# battery_box2.net
KiCad netlist of a schematic drawn in EAGLE
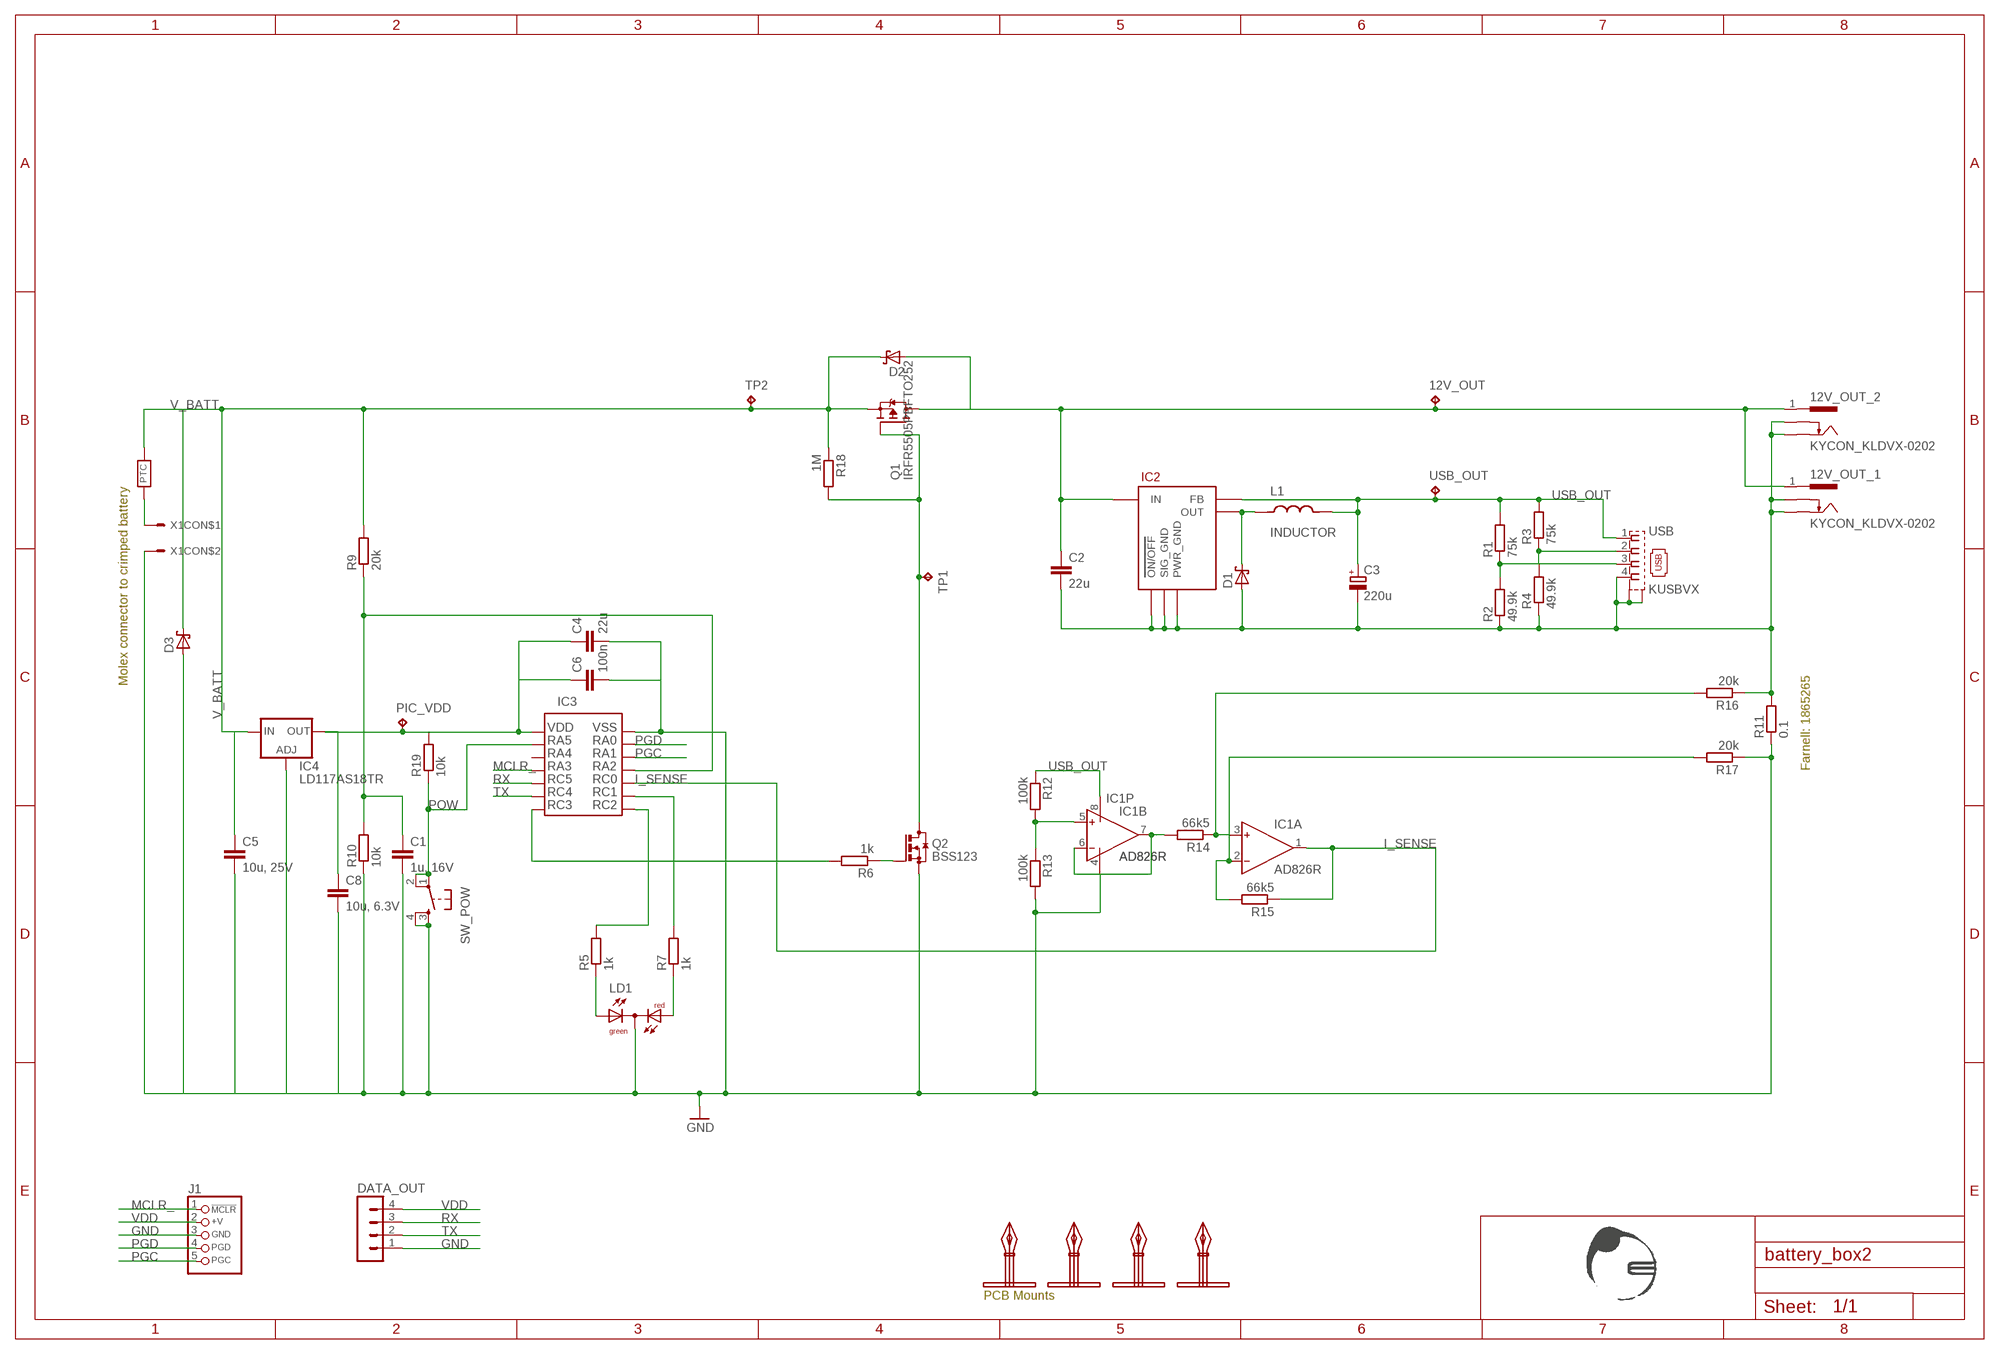
[diagram p0: schematic, sheet 1]

(export (version "E")
  (design (tool "Eeschema 10.0.6"))
  (components
    (comp (ref "12V_OUT")
      (value "TPTP20R")
      (footprint "eagle-import:TP20R")
      (libsource (lib "eagle-import") (part "TPTP20R"))
    )
    (comp (ref "12V_OUT_1")
      (value "KYCON_KLDVX-0202")
      (footprint "eagle-import:KYCON_KLVDX_2020_B")
      (libsource (lib "eagle-import") (part "KYCON_KLDVX-0202"))
    )
    (comp (ref "12V_OUT_2")
      (value "KYCON_KLDVX-0202")
      (footprint "eagle-import:KYCON_KLVDX_2020_B")
      (libsource (lib "eagle-import") (part "KYCON_KLDVX-0202"))
    )
    (comp (ref "C1")
      (value "1u, 16V")
      (footprint "eagle-import:C0805")
      (libsource (lib "eagle-import") (part "C-EUC0805"))
    )
    (comp (ref "C2")
      (value "22u")
      (footprint "eagle-import:C1210")
      (libsource (lib "eagle-import") (part "C-EUC1210"))
    )
    (comp (ref "C3")
      (value "220u")
      (footprint "eagle-import:PANASONIC_E")
      (libsource (lib "eagle-import") (part "CPOL-EUE"))
    )
    (comp (ref "C4")
      (value "22u")
      (footprint "eagle-import:C0805")
      (libsource (lib "eagle-import") (part "C-EUC0805"))
    )
    (comp (ref "C5")
      (value "10u, 25V")
      (footprint "eagle-import:C1210")
      (libsource (lib "eagle-import") (part "C-EUC1210"))
    )
    (comp (ref "C6")
      (value "100n")
      (footprint "eagle-import:C0402")
      (libsource (lib "eagle-import") (part "C-EUC0402"))
    )
    (comp (ref "C8")
      (value "10u, 6.3V")
      (footprint "eagle-import:C0805")
      (libsource (lib "eagle-import") (part "C-EUC0805"))
    )
    (comp (ref "D1")
      (value "SCHOTTKY-DIODESMD")
      (footprint "eagle-import:SMB")
      (libsource (lib "eagle-import") (part "SCHOTTKY-DIODESMD"))
    )
    (comp (ref "D2")
      (value "SCHOTTKY-DIODESMC")
      (footprint "eagle-import:SMC")
      (libsource (lib "eagle-import") (part "SCHOTTKY-DIODESMC"))
    )
    (comp (ref "D3")
      (value "SCHOTTKY-DIODESMC")
      (footprint "eagle-import:SMC")
      (libsource (lib "eagle-import") (part "SCHOTTKY-DIODESMC"))
    )
    (comp (ref "DATA_OUT")
      (value "MA04-1")
      (footprint "eagle-import:MA04-1")
      (libsource (lib "eagle-import") (part "MA04-1"))
    )
    (comp (ref "IC1")
      (value "AD826R")
      (footprint "eagle-import:SO8")
      (libsource (lib "eagle-import") (part "AD826R"))
    )
    (comp (ref "IC2")
      (value "LM2574")
      (footprint "eagle-import:SO14W")
      (libsource (lib "eagle-import") (part "LM2574"))
    )
    (comp (ref "IC3")
      (value "PIC16F1824")
      (footprint "eagle-import:SO-14")
      (libsource (lib "eagle-import") (part "PIC16F1824"))
    )
    (comp (ref "IC4")
      (value "LD117AS18TR")
      (footprint "eagle-import:SOT223")
      (libsource (lib "eagle-import") (part "LD117A?S18TR"))
    )
    (comp (ref "J1")
      (value "CON_HEADER_PRG_PIC_ICSPA")
      (footprint "eagle-import:HEADER_PRG_1X05")
      (libsource (lib "eagle-import") (part "CON_HEADER_PRG_PIC_ICSPA"))
    )
    (comp (ref "L1")
      (value "INDUCTOR")
      (footprint "eagle-import:SMD_INDUCTOR")
      (libsource (lib "eagle-import") (part "INDUCTOR"))
    )
    (comp (ref "LD1")
      (value "DUOLED-RG-C")
      (footprint "eagle-import:DUOLED-C-5MM")
      (libsource (lib "eagle-import") (part "DUOLED-RG-C"))
    )
    (comp (ref "PIC_VDD")
      (value "TPTP14R")
      (footprint "eagle-import:TP14R")
      (libsource (lib "eagle-import") (part "TPTP14R"))
    )
    (comp (ref "Q1")
      (value "IRFR5505PBFTO252")
      (footprint "eagle-import:TO252")
      (libsource (lib "eagle-import") (part "IRFR5505PBFTO252"))
    )
    (comp (ref "Q2")
      (value "BSS123")
      (footprint "eagle-import:SOT23")
      (libsource (lib "eagle-import") (part "BSS123"))
    )
    (comp (ref "R1")
      (value "75k")
      (footprint "eagle-import:R0805")
      (libsource (lib "eagle-import") (part "R-EU_R0805"))
    )
    (comp (ref "R2")
      (value "49.9k")
      (footprint "eagle-import:R0805")
      (libsource (lib "eagle-import") (part "R-EU_R0805"))
    )
    (comp (ref "R3")
      (value "75k")
      (footprint "eagle-import:R0805")
      (libsource (lib "eagle-import") (part "R-EU_R0805"))
    )
    (comp (ref "R4")
      (value "49.9k")
      (footprint "eagle-import:R0805")
      (libsource (lib "eagle-import") (part "R-EU_R0805"))
    )
    (comp (ref "R5")
      (value "1k")
      (footprint "eagle-import:R0805")
      (libsource (lib "eagle-import") (part "R-EU_R0805"))
    )
    (comp (ref "R6")
      (value "1k")
      (footprint "eagle-import:R0805")
      (libsource (lib "eagle-import") (part "R-EU_R0805"))
    )
    (comp (ref "R7")
      (value "1k")
      (footprint "eagle-import:R0805")
      (libsource (lib "eagle-import") (part "R-EU_R0805"))
    )
    (comp (ref "R9")
      (value "20k")
      (footprint "eagle-import:R0805")
      (libsource (lib "eagle-import") (part "R-EU_R0805"))
    )
    (comp (ref "R10")
      (value "10k")
      (footprint "eagle-import:R0805")
      (libsource (lib "eagle-import") (part "R-EU_R0805"))
    )
    (comp (ref "R11")
      (value "0.1")
      (footprint "eagle-import:R2512")
      (libsource (lib "eagle-import") (part "R-EU_R2512"))
    )
    (comp (ref "R12")
      (value "100k")
      (footprint "eagle-import:R0805")
      (libsource (lib "eagle-import") (part "R-EU_R0805"))
    )
    (comp (ref "R13")
      (value "100k")
      (footprint "eagle-import:R0805")
      (libsource (lib "eagle-import") (part "R-EU_R0805"))
    )
    (comp (ref "R14")
      (value "66k5")
      (footprint "eagle-import:R0805")
      (libsource (lib "eagle-import") (part "R-EU_R0805"))
    )
    (comp (ref "R15")
      (value "66k5")
      (footprint "eagle-import:R0805")
      (libsource (lib "eagle-import") (part "R-EU_R0805"))
    )
    (comp (ref "R16")
      (value "20k")
      (footprint "eagle-import:R0805")
      (libsource (lib "eagle-import") (part "R-EU_R0805"))
    )
    (comp (ref "R17")
      (value "20k")
      (footprint "eagle-import:R0805")
      (libsource (lib "eagle-import") (part "R-EU_R0805"))
    )
    (comp (ref "R18")
      (value "1M")
      (footprint "eagle-import:R0805")
      (libsource (lib "eagle-import") (part "R-EU_R0805"))
    )
    (comp (ref "R19")
      (value "10k")
      (footprint "eagle-import:R0805")
      (libsource (lib "eagle-import") (part "R-EU_R0805"))
    )
    (comp (ref "SW_POW")
      (value "TAC_SWITCHPTH")
      (footprint "eagle-import:TACTILE-PTH")
      (libsource (lib "eagle-import") (part "TAC_SWITCHPTH"))
    )
    (comp (ref "TP1")
      (value "TPTP14R")
      (footprint "eagle-import:TP14R")
      (libsource (lib "eagle-import") (part "TPTP14R"))
    )
    (comp (ref "TP2")
      (value "TPTP14R")
      (footprint "eagle-import:TP14R")
      (libsource (lib "eagle-import") (part "TPTP14R"))
    )
    (comp (ref "U$1")
      (value "EQUINOX_LOGO_SMALL")
      (footprint "eagle-import:EQUINOX_LOGO_SMALL")
      (libsource (lib "eagle-import") (part "EQUINOX_LOGO_SMALL"))
    )
    (comp (ref "U$2")
      (value "PTC")
      (footprint "eagle-import:MINISMDC260F")
      (libsource (lib "eagle-import") (part "PTC"))
    )
    (comp (ref "U$5")
      (value "PCB_MOUNT_RICHO")
      (footprint "eagle-import:PCBMOUNT")
      (libsource (lib "eagle-import") (part "PCB_MOUNT_RICHO"))
    )
    (comp (ref "U$6")
      (value "PCB_MOUNT_RICHO")
      (footprint "eagle-import:PCBMOUNT")
      (libsource (lib "eagle-import") (part "PCB_MOUNT_RICHO"))
    )
    (comp (ref "U$7")
      (value "PCB_MOUNT_RICHO")
      (footprint "eagle-import:PCBMOUNT")
      (libsource (lib "eagle-import") (part "PCB_MOUNT_RICHO"))
    )
    (comp (ref "U$8")
      (value "PCB_MOUNT_RICHO")
      (footprint "eagle-import:PCBMOUNT")
      (libsource (lib "eagle-import") (part "PCB_MOUNT_RICHO"))
    )
    (comp (ref "USB")
      (value "KUSBVX")
      (footprint "eagle-import:KUSBVX")
      (libsource (lib "eagle-import") (part "KUSBVX"))
    )
    (comp (ref "USB_OUT")
      (value "TPTP20R")
      (footprint "eagle-import:TP20R")
      (libsource (lib "eagle-import") (part "TPTP20R"))
    )
    (comp (ref "X1")
      (value "CON_MOLEX_39_29_1028")
      (footprint "eagle-import:MOLEX_39_29_1028")
      (libsource (lib "eagle-import") (part "CON_MOLEX_39_29_1028"))
    )
  )
  (nets
    (net (code "1") (name "/I_SENSE") (class "Default")
      (node (ref "IC1") (pin "1") (pinfunction "OUT_1") (pintype "output"))
      (node (ref "IC3") (pin "10") (pinfunction "P$10_10") (pintype "bidirectional"))
      (node (ref "R15") (pin "1") (pinfunction "1_1") (pintype "passive"))
    )
    (net (code "2") (name "/MCLR_") (class "Default")
      (node (ref "IC3") (pin "4") (pinfunction "P$4_4") (pintype "bidirectional"))
      (node (ref "J1") (pin "1") (pinfunction "/MCLR_1") (pintype "passive"))
    )
    (net (code "3") (name "/PGC") (class "Default")
      (node (ref "IC3") (pin "12") (pinfunction "P$12_12") (pintype "bidirectional"))
      (node (ref "J1") (pin "5") (pinfunction "PGC_5") (pintype "passive"))
    )
    (net (code "4") (name "/PGD") (class "Default")
      (node (ref "IC3") (pin "13") (pinfunction "P$13_13") (pintype "bidirectional"))
      (node (ref "J1") (pin "4") (pinfunction "PGD_4") (pintype "passive"))
    )
    (net (code "5") (name "/POW") (class "Default")
      (node (ref "IC3") (pin "2") (pinfunction "P$2_2") (pintype "bidirectional"))
      (node (ref "R19") (pin "1") (pinfunction "1_1") (pintype "passive"))
      (node (ref "SW_POW") (pin "1") (pinfunction "1_1") (pintype "passive"))
      (node (ref "SW_POW") (pin "2") (pinfunction "2_2") (pintype "passive"))
    )
    (net (code "6") (name "/RX") (class "Default")
      (node (ref "DATA_OUT") (pin "3") (pinfunction "3_3") (pintype "passive"))
      (node (ref "IC3") (pin "5") (pinfunction "P$5_5") (pintype "bidirectional"))
    )
    (net (code "7") (name "/TX") (class "Default")
      (node (ref "DATA_OUT") (pin "2") (pinfunction "2_2") (pintype "passive"))
      (node (ref "IC3") (pin "6") (pinfunction "P$6_6") (pintype "bidirectional"))
    )
    (net (code "8") (name "/USB_OUT") (class "Default")
      (node (ref "C3") (pin "+") (pinfunction "+_+") (pintype "passive"))
      (node (ref "IC1") (pin "8") (pinfunction "V+_8") (pintype "power_in"))
      (node (ref "IC2") (pin "3") (pinfunction "FB_3") (pintype "bidirectional"))
      (node (ref "L1") (pin "P$2") (pinfunction "P$2_P$2") (pintype "bidirectional"))
      (node (ref "R1") (pin "2") (pinfunction "2_2") (pintype "passive"))
      (node (ref "R12") (pin "1") (pinfunction "1_1") (pintype "passive"))
      (node (ref "R3") (pin "2") (pinfunction "2_2") (pintype "passive"))
      (node (ref "USB") (pin "1") (pinfunction "1_1") (pintype "passive"))
      (node (ref "USB_OUT") (pin "TP") (pinfunction "TP_TP") (pintype "input"))
    )
    (net (code "9") (name "/VDD") (class "Default")
      (node (ref "C4") (pin "1") (pinfunction "1_1") (pintype "passive"))
      (node (ref "C6") (pin "1") (pinfunction "1_1") (pintype "passive"))
      (node (ref "C8") (pin "1") (pinfunction "1_1") (pintype "passive"))
      (node (ref "DATA_OUT") (pin "4") (pinfunction "4_4") (pintype "passive"))
      (node (ref "IC3") (pin "1") (pinfunction "P$1_1") (pintype "bidirectional"))
      (node (ref "IC4") (pin "4") (pinfunction "OUT_4") (pintype "passive"))
      (node (ref "J1") (pin "2") (pinfunction "+V_2") (pintype "passive"))
      (node (ref "PIC_VDD") (pin "TP") (pinfunction "TP_TP") (pintype "input"))
      (node (ref "R19") (pin "2") (pinfunction "2_2") (pintype "passive"))
    )
    (net (code "10") (name "/V_BATT") (class "Default")
      (node (ref "C5") (pin "1") (pinfunction "1_1") (pintype "passive"))
      (node (ref "D2") (pin "C") (pinfunction "C_C") (pintype "passive"))
      (node (ref "D3") (pin "C") (pinfunction "C_C") (pintype "passive"))
      (node (ref "IC4") (pin "3") (pinfunction "IN_3") (pintype "input"))
      (node (ref "Q1") (pin "2") (pinfunction "S_2") (pintype "passive"))
      (node (ref "R18") (pin "1") (pinfunction "1_1") (pintype "passive"))
      (node (ref "R9") (pin "2") (pinfunction "2_2") (pintype "passive"))
      (node (ref "TP2") (pin "TP") (pinfunction "TP_TP") (pintype "input"))
      (node (ref "U$2") (pin "P$2") (pinfunction "P$2_P$2") (pintype "bidirectional"))
    )
    (net (code "11") (name "GND") (class "Default")
      (node (ref "C1") (pin "2") (pinfunction "2_2") (pintype "passive"))
      (node (ref "C4") (pin "2") (pinfunction "2_2") (pintype "passive"))
      (node (ref "C5") (pin "2") (pinfunction "2_2") (pintype "passive"))
      (node (ref "C6") (pin "2") (pinfunction "2_2") (pintype "passive"))
      (node (ref "C8") (pin "2") (pinfunction "2_2") (pintype "passive"))
      (node (ref "D3") (pin "A") (pinfunction "A_A") (pintype "passive"))
      (node (ref "DATA_OUT") (pin "1") (pinfunction "1_1") (pintype "passive"))
      (node (ref "IC1") (pin "4") (pinfunction "V-_4") (pintype "power_in"))
      (node (ref "IC3") (pin "14") (pinfunction "P$14_14") (pintype "bidirectional"))
      (node (ref "IC4") (pin "1") (pinfunction "ADJ_1") (pintype "input"))
      (node (ref "J1") (pin "3") (pinfunction "GND_3") (pintype "passive"))
      (node (ref "LD1") (pin "C") (pinfunction "C_C") (pintype "passive"))
      (node (ref "Q2") (pin "2") (pinfunction "S_2") (pintype "passive"))
      (node (ref "R10") (pin "1") (pinfunction "1_1") (pintype "passive"))
      (node (ref "R11") (pin "1") (pinfunction "1_1") (pintype "passive"))
      (node (ref "R13") (pin "2") (pinfunction "2_2") (pintype "passive"))
      (node (ref "R17") (pin "1") (pinfunction "1_1") (pintype "passive"))
      (node (ref "SW_POW") (pin "3") (pinfunction "3_3") (pintype "passive"))
      (node (ref "SW_POW") (pin "4") (pinfunction "4_4") (pintype "passive"))
      (node (ref "X1") (pin "P$2") (pinfunction "S_P$2") (pintype "passive"))
    )
    (net (code "12") (name "Net-(12V_OUT_1-PAD1)") (class "Default")
      (node (ref "12V_OUT") (pin "TP") (pinfunction "TP_TP") (pintype "input"))
      (node (ref "12V_OUT_1") (pin "1") (pinfunction "PAD1_1") (pintype "passive"))
      (node (ref "12V_OUT_2") (pin "1") (pinfunction "PAD1_1") (pintype "passive"))
      (node (ref "C2") (pin "1") (pinfunction "1_1") (pintype "passive"))
      (node (ref "D2") (pin "A") (pinfunction "A_A") (pintype "passive"))
      (node (ref "IC2") (pin "10") (pinfunction "IN_10") (pintype "bidirectional"))
      (node (ref "Q1") (pin "3") (pinfunction "D_3") (pintype "passive"))
    )
    (net (code "13") (name "Net-(12V_OUT_1-PAD2)") (class "Default")
      (node (ref "12V_OUT_1") (pin "2") (pinfunction "PAD2_2") (pintype "passive"))
      (node (ref "12V_OUT_1") (pin "3") (pinfunction "PAD3_3") (pintype "passive"))
      (node (ref "12V_OUT_2") (pin "2") (pinfunction "PAD2_2") (pintype "passive"))
      (node (ref "12V_OUT_2") (pin "3") (pinfunction "PAD3_3") (pintype "passive"))
      (node (ref "C2") (pin "2") (pinfunction "2_2") (pintype "passive"))
      (node (ref "C3") (pin "-") (pinfunction "-_-") (pintype "passive"))
      (node (ref "D1") (pin "A") (pinfunction "A_A") (pintype "passive"))
      (node (ref "IC2") (pin "4") (pinfunction "SIG_GND_4") (pintype "bidirectional"))
      (node (ref "IC2") (pin "5") (pinfunction "ON/OFF_5") (pintype "bidirectional"))
      (node (ref "IC2") (pin "6") (pinfunction "PWR_GND_6") (pintype "bidirectional"))
      (node (ref "R11") (pin "2") (pinfunction "2_2") (pintype "passive"))
      (node (ref "R16") (pin "1") (pinfunction "1_1") (pintype "passive"))
      (node (ref "R2") (pin "1") (pinfunction "1_1") (pintype "passive"))
      (node (ref "R4") (pin "1") (pinfunction "1_1") (pintype "passive"))
      (node (ref "USB") (pin "4") (pinfunction "4_4") (pintype "passive"))
      (node (ref "USB") (pin "M1") (pinfunction "S1_M1") (pintype "passive"))
      (node (ref "USB") (pin "M2") (pinfunction "S2_M2") (pintype "passive"))
    )
    (net (code "14") (name "Net-(IC1A-IN+)") (class "Default")
      (node (ref "IC1") (pin "3") (pinfunction "IN+_3") (pintype "input"))
      (node (ref "R14") (pin "1") (pinfunction "1_1") (pintype "passive"))
      (node (ref "R16") (pin "2") (pinfunction "2_2") (pintype "passive"))
    )
    (net (code "15") (name "Net-(IC1A-IN-)") (class "Default")
      (node (ref "IC1") (pin "2") (pinfunction "IN-_2") (pintype "input"))
      (node (ref "R15") (pin "2") (pinfunction "2_2") (pintype "passive"))
      (node (ref "R17") (pin "2") (pinfunction "2_2") (pintype "passive"))
    )
    (net (code "16") (name "Net-(IC1B-IN+)") (class "Default")
      (node (ref "IC1") (pin "5") (pinfunction "IN+_5") (pintype "input"))
      (node (ref "R12") (pin "2") (pinfunction "2_2") (pintype "passive"))
      (node (ref "R13") (pin "1") (pinfunction "1_1") (pintype "passive"))
    )
    (net (code "17") (name "Net-(IC1B-IN-)") (class "Default")
      (node (ref "IC1") (pin "6") (pinfunction "IN-_6") (pintype "input"))
      (node (ref "IC1") (pin "7") (pinfunction "OUT_7") (pintype "output"))
      (node (ref "R14") (pin "2") (pinfunction "2_2") (pintype "passive"))
    )
    (net (code "18") (name "Net-(IC2-OUT)") (class "Default")
      (node (ref "D1") (pin "C") (pinfunction "C_C") (pintype "passive"))
      (node (ref "IC2") (pin "12") (pinfunction "OUT_12") (pintype "bidirectional"))
      (node (ref "L1") (pin "P$1") (pinfunction "P$1_P$1") (pintype "bidirectional"))
    )
    (net (code "19") (name "Net-(IC3-P$7)") (class "Default")
      (node (ref "IC3") (pin "7") (pinfunction "P$7_7") (pintype "bidirectional"))
      (node (ref "R6") (pin "2") (pinfunction "2_2") (pintype "passive"))
    )
    (net (code "20") (name "Net-(IC3-P$8)") (class "Default")
      (node (ref "IC3") (pin "8") (pinfunction "P$8_8") (pintype "bidirectional"))
      (node (ref "R5") (pin "2") (pinfunction "2_2") (pintype "passive"))
    )
    (net (code "21") (name "Net-(IC3-P$9)") (class "Default")
      (node (ref "IC3") (pin "9") (pinfunction "P$9_9") (pintype "bidirectional"))
      (node (ref "R7") (pin "2") (pinfunction "2_2") (pintype "passive"))
    )
    (net (code "22") (name "Net-(IC3-P$11)") (class "Default")
      (node (ref "C1") (pin "1") (pinfunction "1_1") (pintype "passive"))
      (node (ref "IC3") (pin "11") (pinfunction "P$11_11") (pintype "bidirectional"))
      (node (ref "R10") (pin "2") (pinfunction "2_2") (pintype "passive"))
      (node (ref "R9") (pin "1") (pinfunction "1_1") (pintype "passive"))
    )
    (net (code "23") (name "Net-(LD1-AG)") (class "Default")
      (node (ref "LD1") (pin "AX") (pinfunction "AG_AX") (pintype "passive"))
      (node (ref "R5") (pin "1") (pinfunction "1_1") (pintype "passive"))
    )
    (net (code "24") (name "Net-(LD1-PadAR)") (class "Default")
      (node (ref "LD1") (pin "AR") (pinfunction "AR_AR") (pintype "passive"))
      (node (ref "R7") (pin "1") (pinfunction "1_1") (pintype "passive"))
    )
    (net (code "25") (name "Net-(Q1-G)") (class "Default")
      (node (ref "Q1") (pin "1") (pinfunction "G_1") (pintype "passive"))
      (node (ref "Q2") (pin "3") (pinfunction "D_3") (pintype "passive"))
      (node (ref "R18") (pin "2") (pinfunction "2_2") (pintype "passive"))
      (node (ref "TP1") (pin "TP") (pinfunction "TP_TP") (pintype "input"))
    )
    (net (code "26") (name "Net-(Q2-G)") (class "Default")
      (node (ref "Q2") (pin "1") (pinfunction "G_1") (pintype "passive"))
      (node (ref "R6") (pin "1") (pinfunction "1_1") (pintype "passive"))
    )
    (net (code "27") (name "Net-(R1-Pad1)") (class "Default")
      (node (ref "R1") (pin "1") (pinfunction "1_1") (pintype "passive"))
      (node (ref "R2") (pin "2") (pinfunction "2_2") (pintype "passive"))
      (node (ref "USB") (pin "3") (pinfunction "3_3") (pintype "passive"))
    )
    (net (code "28") (name "Net-(R3-Pad1)") (class "Default")
      (node (ref "R3") (pin "1") (pinfunction "1_1") (pintype "passive"))
      (node (ref "R4") (pin "2") (pinfunction "2_2") (pintype "passive"))
      (node (ref "USB") (pin "2") (pinfunction "2_2") (pintype "passive"))
    )
    (net (code "29") (name "Net-(X1A-S)") (class "Default")
      (node (ref "U$2") (pin "P$1") (pinfunction "P$1_P$1") (pintype "bidirectional"))
      (node (ref "X1") (pin "P$1") (pinfunction "S_P$1") (pintype "passive"))
    )
    (net (code "30") (name "unconnected-(IC3-P$3-Pad3)") (class "Default")
      (node (ref "IC3") (pin "3") (pinfunction "P$3_3") (pintype "bidirectional"))
    )
  )
)
